# SmartThermo2_1.net
KiCad netlist of a schematic drawn in EAGLE
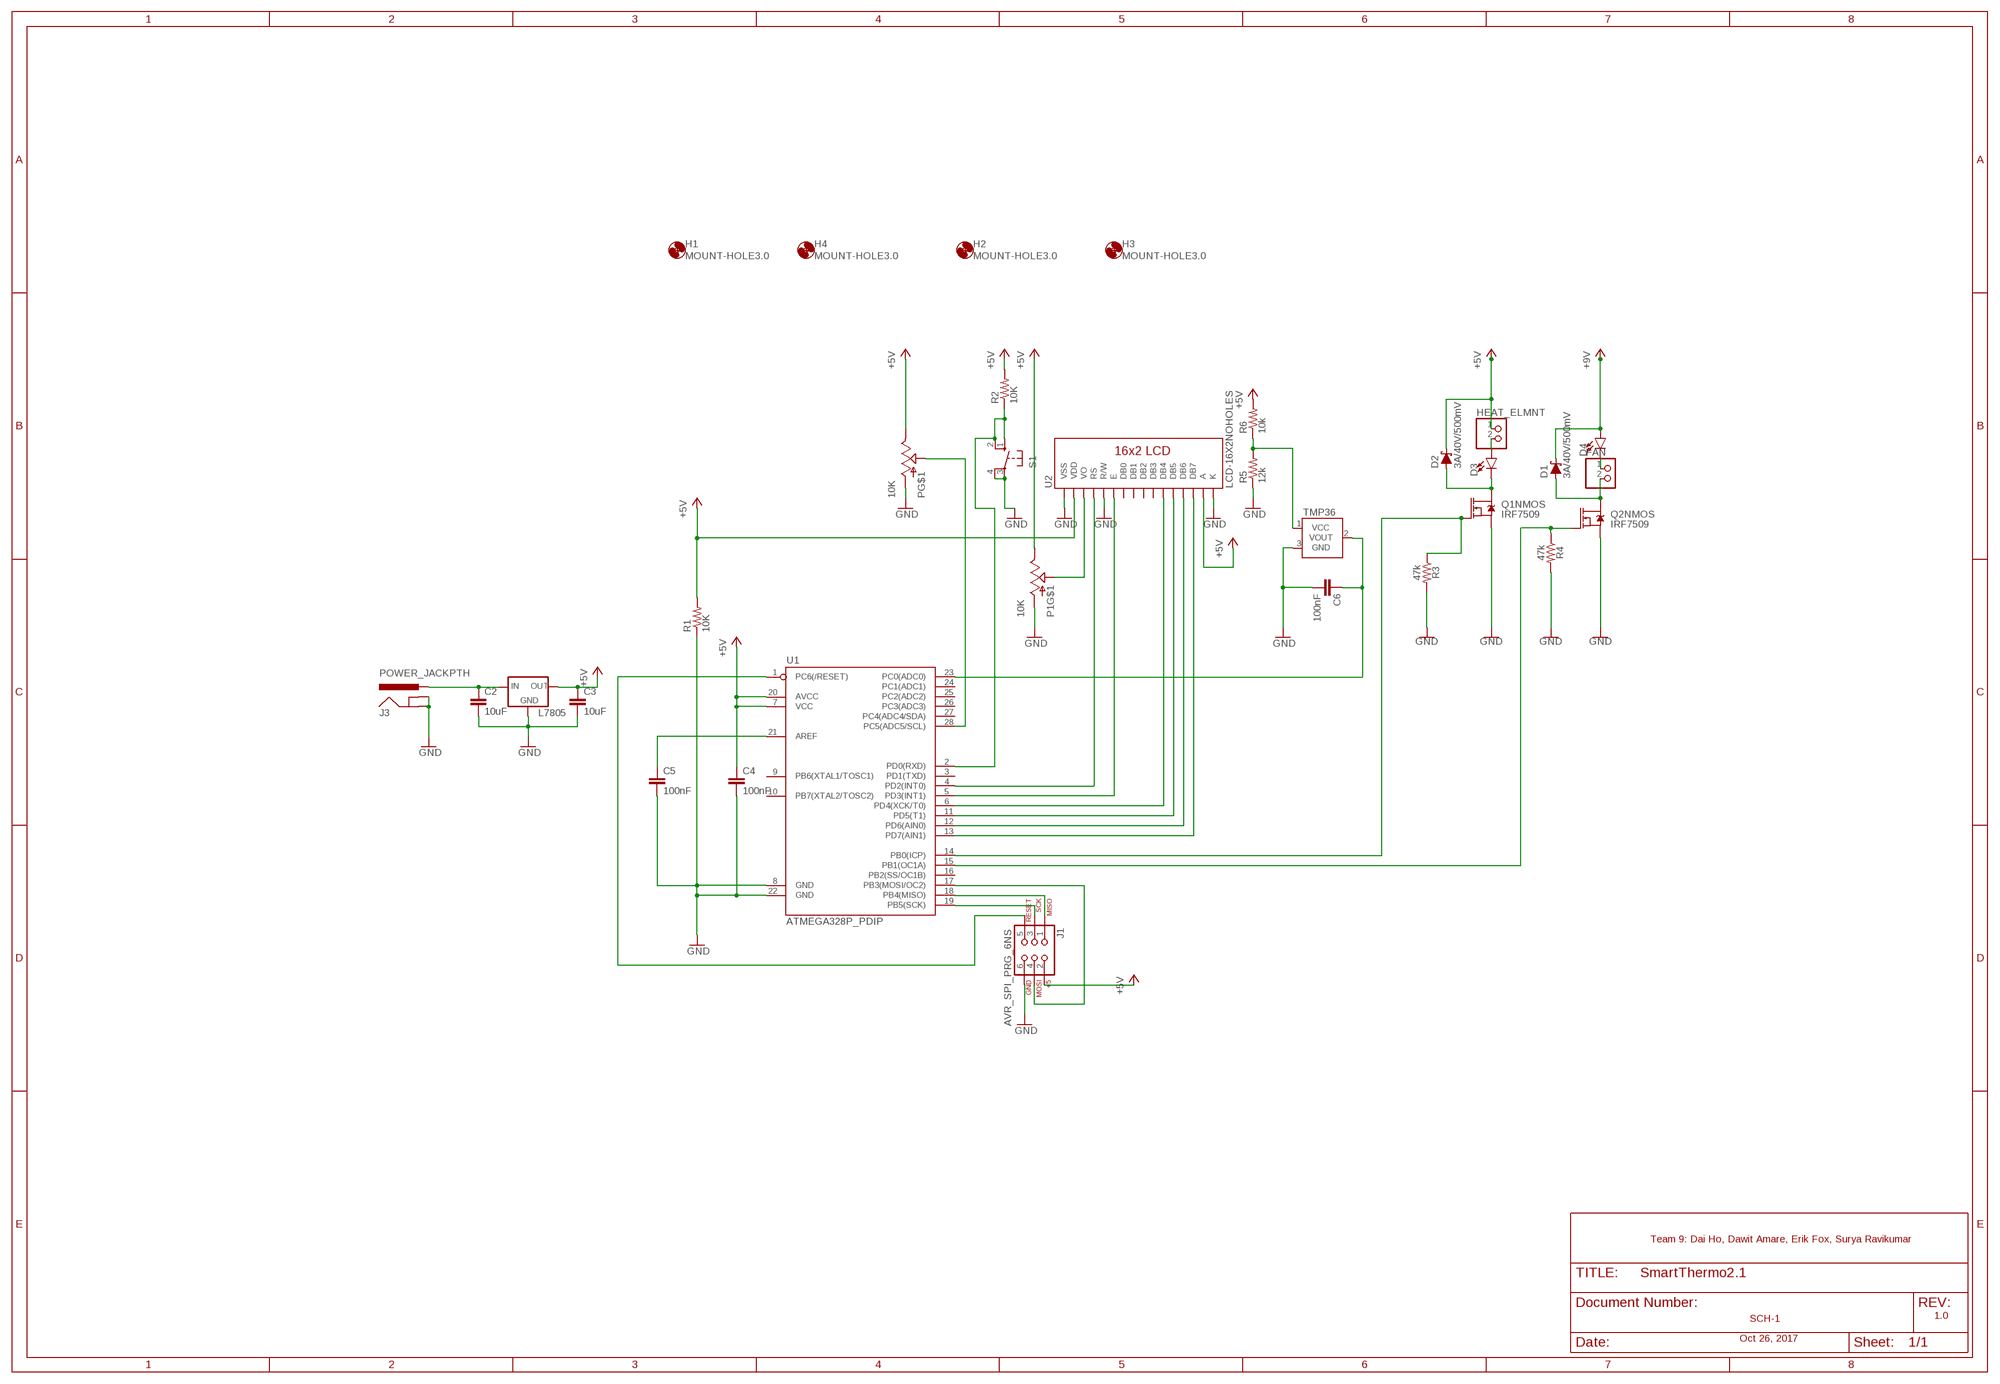
[diagram p0: schematic, sheet 1]

(export (version "E")
  (design (tool "Eeschema 10.0.6"))
  (components
    (comp (ref "C2")
      (value "10uF")
      (footprint "eagle-import:C7.5B3")
      (libsource (lib "eagle-import") (part "C7.5/3"))
    )
    (comp (ref "C3")
      (value "10uF")
      (footprint "eagle-import:C7.5B3")
      (libsource (lib "eagle-import") (part "C7.5/3"))
    )
    (comp (ref "C4")
      (value "100nF")
      (footprint "eagle-import:C2.5-2")
      (libsource (lib "eagle-import") (part "C2.5/2"))
    )
    (comp (ref "C5")
      (value "100nF")
      (footprint "eagle-import:C2.5-2")
      (libsource (lib "eagle-import") (part "C2.5/2"))
    )
    (comp (ref "C6")
      (value "100nF")
      (footprint "eagle-import:C2.5-2")
      (libsource (lib "eagle-import") (part "C2.5/2"))
    )
    (comp (ref "D1")
      (value "3A/40V/500mV")
      (footprint "eagle-import:SMA-DIODE")
      (libsource (lib "eagle-import") (part "DIODE-SCHOTTKY-B340A"))
    )
    (comp (ref "D2")
      (value "3A/40V/500mV")
      (footprint "eagle-import:SMA-DIODE")
      (libsource (lib "eagle-import") (part "DIODE-SCHOTTKY-B340A"))
    )
    (comp (ref "D3")
      (value "LED3MM")
      (footprint "eagle-import:LED_3MM")
      (libsource (lib "eagle-import") (part "LED3MM"))
    )
    (comp (ref "D4")
      (value "LED3MM")
      (footprint "eagle-import:LED_3MM")
      (libsource (lib "eagle-import") (part "LED3MM"))
    )
    (comp (ref "FAN")
      (value "PINHD-1X2/90")
      (footprint "eagle-import:1X02_90")
      (libsource (lib "eagle-import") (part "PINHD-1X2/90"))
    )
    (comp (ref "H1")
      (value "MOUNT-HOLE3.0")
      (footprint "eagle-import:3,0")
      (libsource (lib "eagle-import") (part "MOUNT-HOLE3.0"))
    )
    (comp (ref "H2")
      (value "MOUNT-HOLE3.0")
      (footprint "eagle-import:3,0")
      (libsource (lib "eagle-import") (part "MOUNT-HOLE3.0"))
    )
    (comp (ref "H3")
      (value "MOUNT-HOLE3.0")
      (footprint "eagle-import:3,0")
      (libsource (lib "eagle-import") (part "MOUNT-HOLE3.0"))
    )
    (comp (ref "H4")
      (value "MOUNT-HOLE3.0")
      (footprint "eagle-import:3,0")
      (libsource (lib "eagle-import") (part "MOUNT-HOLE3.0"))
    )
    (comp (ref "HEAT_ELMNT")
      (value "PINHD-1X2/90")
      (footprint "eagle-import:1X02_90")
      (libsource (lib "eagle-import") (part "PINHD-1X2/90"))
    )
    (comp (ref "J1")
      (value "AVR_SPI_PRG_6NS")
      (footprint "eagle-import:2X3-NS")
      (libsource (lib "eagle-import") (part "AVR_SPI_PRG_6NS"))
    )
    (comp (ref "J3")
      (value "POWER_JACKPTH")
      (footprint "eagle-import:POWER_JACK_PTH")
      (libsource (lib "eagle-import") (part "POWER_JACKPTH"))
    )
    (comp (ref "L7805")
      (value "78XXL")
      (footprint "eagle-import:78XXL")
      (libsource (lib "eagle-import") (part "78XXL"))
    )
    (comp (ref "P")
      (value "10K")
      (footprint "eagle-import:POT_PTH")
      (libsource (lib "eagle-import") (part "POT_SWITCHPOT_PTH"))
    )
    (comp (ref "P1")
      (value "10K")
      (footprint "eagle-import:POT_PTH")
      (libsource (lib "eagle-import") (part "POT_SWITCHPOT_PTH"))
    )
    (comp (ref "Q1")
      (value "IRF7509")
      (footprint "eagle-import:MSOP8")
      (libsource (lib "eagle-import") (part "IRF7509"))
    )
    (comp (ref "Q2")
      (value "IRF7509")
      (footprint "eagle-import:MSOP8")
      (libsource (lib "eagle-import") (part "IRF7509"))
    )
    (comp (ref "R1")
      (value "10K")
      (footprint "eagle-import:1206")
      (libsource (lib "eagle-import") (part "RESISTOR1206"))
    )
    (comp (ref "R2")
      (value "10K")
      (footprint "eagle-import:1206")
      (libsource (lib "eagle-import") (part "RESISTOR1206"))
    )
    (comp (ref "R3")
      (value "47k")
      (footprint "eagle-import:0603")
      (libsource (lib "eagle-import") (part "47KOHM-0603-1/10W-1%"))
    )
    (comp (ref "R4")
      (value "47k")
      (footprint "eagle-import:0603")
      (libsource (lib "eagle-import") (part "47KOHM-0603-1/10W-1%"))
    )
    (comp (ref "R5")
      (value "12k")
      (footprint "eagle-import:0204_5")
      (libsource (lib "eagle-import") (part "R-US_0204/5"))
    )
    (comp (ref "R6")
      (value "10k")
      (footprint "eagle-import:0204_5")
      (libsource (lib "eagle-import") (part "R-US_0204/5"))
    )
    (comp (ref "S1")
      (value "10-XX")
      (footprint "eagle-import:B3F-10XX")
      (fields (field (name "MPN") "B3F-1000"))
      (libsource (lib "eagle-import") (part "10-XX"))
    )
    (comp (ref "TMP36")
      (value "TMP36GT9")
      (footprint "eagle-import:TO-92")
      (libsource (lib "eagle-import") (part "TMP36GT9"))
    )
    (comp (ref "U1")
      (value "ATMEGA328P_PDIP")
      (footprint "eagle-import:DIL28-3")
      (libsource (lib "eagle-import") (part "ATMEGA328P_PDIP"))
    )
    (comp (ref "U2")
      (value "LCD-16X2NOHOLES")
      (footprint "eagle-import:LCD-16X2_NOHOLES")
      (libsource (lib "eagle-import") (part "LCD-16X2NOHOLES"))
    )
  )
  (nets
    (net (code "1") (name "+5V") (class "Default")
      (node (ref "C3") (pin "1") (pinfunction "1_1") (pintype "passive"))
      (node (ref "C4") (pin "1") (pinfunction "1_1") (pintype "passive"))
      (node (ref "D1") (pin "C") (pinfunction "C_C") (pintype "passive"))
      (node (ref "D2") (pin "C") (pinfunction "C_C") (pintype "passive"))
      (node (ref "D4") (pin "A") (pinfunction "A_A") (pintype "passive"))
      (node (ref "HEAT_ELMNT") (pin "1") (pinfunction "1_1") (pintype "passive"))
      (node (ref "J1") (pin "2") (pinfunction "2_2") (pintype "passive"))
      (node (ref "L7805") (pin "OUT") (pinfunction "OUT_OUT") (pintype "passive"))
      (node (ref "P") (pin "E@2") (pinfunction "E_E@2") (pintype "passive"))
      (node (ref "P1") (pin "E@2") (pinfunction "E_E@2") (pintype "passive"))
      (node (ref "R1") (pin "2") (pinfunction "2_2") (pintype "passive"))
      (node (ref "R2") (pin "2") (pinfunction "2_2") (pintype "passive"))
      (node (ref "R6") (pin "2") (pinfunction "2_2") (pintype "passive"))
      (node (ref "U1") (pin "20") (pinfunction "AVCC_20") (pintype "bidirectional"))
      (node (ref "U1") (pin "7") (pinfunction "VCC_7") (pintype "bidirectional"))
      (node (ref "U2") (pin "15") (pinfunction "A_15") (pintype "power_in"))
      (node (ref "U2") (pin "2") (pinfunction "VDD_2") (pintype "power_in"))
    )
    (net (code "2") (name "GND") (class "Default")
      (node (ref "C2") (pin "2") (pinfunction "2_2") (pintype "passive"))
      (node (ref "C3") (pin "2") (pinfunction "2_2") (pintype "passive"))
      (node (ref "C4") (pin "2") (pinfunction "2_2") (pintype "passive"))
      (node (ref "C5") (pin "2") (pinfunction "2_2") (pintype "passive"))
      (node (ref "C6") (pin "2") (pinfunction "2_2") (pintype "passive"))
      (node (ref "J1") (pin "6") (pinfunction "6_6") (pintype "passive"))
      (node (ref "J3") (pin "GND") (pinfunction "GND_GND") (pintype "bidirectional"))
      (node (ref "J3") (pin "GNDBREAK") (pinfunction "GNDBREAK_GNDBREAK") (pintype "bidirectional"))
      (node (ref "L7805") (pin "GND") (pinfunction "GND_GND") (pintype "input"))
      (node (ref "P") (pin "E@1") (pinfunction "A_E@1") (pintype "passive"))
      (node (ref "P1") (pin "E@1") (pinfunction "A_E@1") (pintype "passive"))
      (node (ref "Q1") (pin "1") (pinfunction "S_1") (pintype "bidirectional"))
      (node (ref "Q2") (pin "1") (pinfunction "S_1") (pintype "bidirectional"))
      (node (ref "R1") (pin "1") (pinfunction "1_1") (pintype "passive"))
      (node (ref "R3") (pin "2") (pinfunction "2_2") (pintype "passive"))
      (node (ref "R4") (pin "2") (pinfunction "2_2") (pintype "passive"))
      (node (ref "R5") (pin "1") (pinfunction "1_1") (pintype "passive"))
      (node (ref "S1") (pin "3") (pinfunction "P_3") (pintype "passive"))
      (node (ref "S1") (pin "4") (pinfunction "P1_4") (pintype "passive"))
      (node (ref "TMP36") (pin "3") (pinfunction "GND_3") (pintype "bidirectional"))
      (node (ref "U1") (pin "22") (pinfunction "GND_22") (pintype "bidirectional"))
      (node (ref "U1") (pin "8") (pinfunction "GND_8") (pintype "bidirectional"))
      (node (ref "U2") (pin "1") (pinfunction "VSS_1") (pintype "power_in"))
      (node (ref "U2") (pin "16") (pinfunction "K_16") (pintype "power_in"))
      (node (ref "U2") (pin "5") (pinfunction "R/W_5") (pintype "input"))
    )
    (net (code "3") (name "Net-(C2-Pad1)") (class "Default")
      (node (ref "C2") (pin "1") (pinfunction "1_1") (pintype "passive"))
      (node (ref "J3") (pin "PWR") (pinfunction "PWR_PWR") (pintype "bidirectional"))
      (node (ref "L7805") (pin "IN") (pinfunction "IN_IN") (pintype "input"))
    )
    (net (code "4") (name "Net-(D1-PadA)") (class "Default")
      (node (ref "D1") (pin "A") (pinfunction "A_A") (pintype "passive"))
      (node (ref "FAN") (pin "2") (pinfunction "2_2") (pintype "passive"))
      (node (ref "Q2") (pin "7") (pinfunction "D_7") (pintype "bidirectional"))
      (node (ref "Q2") (pin "8") (pinfunction "D_8") (pintype "bidirectional"))
    )
    (net (code "5") (name "Net-(D3-C)") (class "Default")
      (node (ref "D2") (pin "A") (pinfunction "A_A") (pintype "passive"))
      (node (ref "D3") (pin "K") (pinfunction "C_K") (pintype "passive"))
      (node (ref "Q1") (pin "7") (pinfunction "D_7") (pintype "bidirectional"))
      (node (ref "Q1") (pin "8") (pinfunction "D_8") (pintype "bidirectional"))
    )
    (net (code "6") (name "Net-(D3-PadA)") (class "Default")
      (node (ref "D3") (pin "A") (pinfunction "A_A") (pintype "passive"))
      (node (ref "HEAT_ELMNT") (pin "2") (pinfunction "2_2") (pintype "passive"))
    )
    (net (code "7") (name "Net-(D4-C)") (class "Default")
      (node (ref "D4") (pin "K") (pinfunction "C_K") (pintype "passive"))
      (node (ref "FAN") (pin "1") (pinfunction "1_1") (pintype "passive"))
    )
    (net (code "8") (name "Net-(P1A-S)") (class "Default")
      (node (ref "P1") (pin "WAND") (pinfunction "S_WAND") (pintype "passive"))
      (node (ref "U2") (pin "3") (pinfunction "VO_3") (pintype "bidirectional"))
    )
    (net (code "9") (name "Net-(PA-S)") (class "Default")
      (node (ref "P") (pin "WAND") (pinfunction "S_WAND") (pintype "passive"))
      (node (ref "U1") (pin "28") (pinfunction "PC5(ADC5/SCL)_28") (pintype "bidirectional"))
    )
    (net (code "10") (name "Net-(Q1A-G)") (class "Default")
      (node (ref "Q1") (pin "2") (pinfunction "G_2") (pintype "bidirectional"))
      (node (ref "R3") (pin "1") (pinfunction "1_1") (pintype "passive"))
      (node (ref "U1") (pin "14") (pinfunction "PB0(ICP)_14") (pintype "bidirectional"))
    )
    (net (code "11") (name "Net-(Q2A-G)") (class "Default")
      (node (ref "Q2") (pin "2") (pinfunction "G_2") (pintype "bidirectional"))
      (node (ref "R4") (pin "1") (pinfunction "1_1") (pintype "passive"))
      (node (ref "U1") (pin "15") (pinfunction "PB1(OC1A)_15") (pintype "bidirectional"))
    )
    (net (code "12") (name "Net-(S1-S)") (class "Default")
      (node (ref "R2") (pin "1") (pinfunction "1_1") (pintype "passive"))
      (node (ref "S1") (pin "1") (pinfunction "S_1") (pintype "passive"))
      (node (ref "S1") (pin "2") (pinfunction "S1_2") (pintype "passive"))
      (node (ref "U1") (pin "2") (pinfunction "PD0(RXD)_2") (pintype "bidirectional"))
    )
    (net (code "13") (name "Net-(TMP36-VCC)") (class "Default")
      (node (ref "R5") (pin "2") (pinfunction "2_2") (pintype "passive"))
      (node (ref "R6") (pin "1") (pinfunction "1_1") (pintype "passive"))
      (node (ref "TMP36") (pin "1") (pinfunction "VCC_1") (pintype "bidirectional"))
    )
    (net (code "14") (name "Net-(TMP36-VOUT)") (class "Default")
      (node (ref "C6") (pin "1") (pinfunction "1_1") (pintype "passive"))
      (node (ref "TMP36") (pin "2") (pinfunction "VOUT_2") (pintype "bidirectional"))
      (node (ref "U1") (pin "23") (pinfunction "PC0(ADC0)_23") (pintype "bidirectional"))
    )
    (net (code "15") (name "Net-(U1-AREF)") (class "Default")
      (node (ref "C5") (pin "1") (pinfunction "1_1") (pintype "passive"))
      (node (ref "U1") (pin "21") (pinfunction "AREF_21") (pintype "bidirectional"))
    )
    (net (code "16") (name "Net-(U1-PB3(MOSI{slash}OC2))") (class "Default")
      (node (ref "J1") (pin "4") (pinfunction "4_4") (pintype "passive"))
      (node (ref "U1") (pin "17") (pinfunction "PB3(MOSI/OC2)_17") (pintype "bidirectional"))
    )
    (net (code "17") (name "Net-(U1-PB4(MISO))") (class "Default")
      (node (ref "J1") (pin "1") (pinfunction "1_1") (pintype "passive"))
      (node (ref "U1") (pin "18") (pinfunction "PB4(MISO)_18") (pintype "bidirectional"))
    )
    (net (code "18") (name "Net-(U1-PB5(SCK))") (class "Default")
      (node (ref "J1") (pin "3") (pinfunction "3_3") (pintype "passive"))
      (node (ref "U1") (pin "19") (pinfunction "PB5(SCK)_19") (pintype "bidirectional"))
    )
    (net (code "19") (name "Net-(U1-PC6({slash}RESET))") (class "Default")
      (node (ref "J1") (pin "5") (pinfunction "5_5") (pintype "passive"))
      (node (ref "U1") (pin "1") (pinfunction "PC6(/RESET)_1") (pintype "bidirectional"))
    )
    (net (code "20") (name "Net-(U1-PD2(INT0))") (class "Default")
      (node (ref "U1") (pin "4") (pinfunction "PD2(INT0)_4") (pintype "bidirectional"))
      (node (ref "U2") (pin "4") (pinfunction "RS_4") (pintype "input"))
    )
    (net (code "21") (name "Net-(U1-PD3(INT1))") (class "Default")
      (node (ref "U1") (pin "5") (pinfunction "PD3(INT1)_5") (pintype "bidirectional"))
      (node (ref "U2") (pin "6") (pinfunction "E_6") (pintype "input"))
    )
    (net (code "22") (name "Net-(U1-PD4(XCK{slash}T0))") (class "Default")
      (node (ref "U1") (pin "6") (pinfunction "PD4(XCK/T0)_6") (pintype "bidirectional"))
      (node (ref "U2") (pin "11") (pinfunction "DB4_11") (pintype "bidirectional"))
    )
    (net (code "23") (name "Net-(U1-PD5(T1))") (class "Default")
      (node (ref "U1") (pin "11") (pinfunction "PD5(T1)_11") (pintype "bidirectional"))
      (node (ref "U2") (pin "12") (pinfunction "DB5_12") (pintype "bidirectional"))
    )
    (net (code "24") (name "Net-(U1-PD6(AIN0))") (class "Default")
      (node (ref "U1") (pin "12") (pinfunction "PD6(AIN0)_12") (pintype "bidirectional"))
      (node (ref "U2") (pin "13") (pinfunction "DB6_13") (pintype "bidirectional"))
    )
    (net (code "25") (name "Net-(U1-PD7(AIN1))") (class "Default")
      (node (ref "U1") (pin "13") (pinfunction "PD7(AIN1)_13") (pintype "bidirectional"))
      (node (ref "U2") (pin "14") (pinfunction "DB7_14") (pintype "bidirectional"))
    )
    (net (code "26") (name "unconnected-(U1-PB2(SS{slash}OC1B)-Pad16)") (class "Default")
      (node (ref "U1") (pin "16") (pinfunction "PB2(SS/OC1B)_16") (pintype "bidirectional"))
    )
    (net (code "27") (name "unconnected-(U1-PB6(XTAL1{slash}TOSC1)-Pad9)") (class "Default")
      (node (ref "U1") (pin "9") (pinfunction "PB6(XTAL1/TOSC1)_9") (pintype "bidirectional"))
    )
    (net (code "28") (name "unconnected-(U1-PB7(XTAL2{slash}TOSC2)-Pad10)") (class "Default")
      (node (ref "U1") (pin "10") (pinfunction "PB7(XTAL2/TOSC2)_10") (pintype "bidirectional"))
    )
    (net (code "29") (name "unconnected-(U1-PC1(ADC1)-Pad24)") (class "Default")
      (node (ref "U1") (pin "24") (pinfunction "PC1(ADC1)_24") (pintype "bidirectional"))
    )
    (net (code "30") (name "unconnected-(U1-PC2(ADC2)-Pad25)") (class "Default")
      (node (ref "U1") (pin "25") (pinfunction "PC2(ADC2)_25") (pintype "bidirectional"))
    )
    (net (code "31") (name "unconnected-(U1-PC3(ADC3)-Pad26)") (class "Default")
      (node (ref "U1") (pin "26") (pinfunction "PC3(ADC3)_26") (pintype "bidirectional"))
    )
    (net (code "32") (name "unconnected-(U1-PC4(ADC4{slash}SDA)-Pad27)") (class "Default")
      (node (ref "U1") (pin "27") (pinfunction "PC4(ADC4/SDA)_27") (pintype "bidirectional"))
    )
    (net (code "33") (name "unconnected-(U1-PD1(TXD)-Pad3)") (class "Default")
      (node (ref "U1") (pin "3") (pinfunction "PD1(TXD)_3") (pintype "bidirectional"))
    )
    (net (code "34") (name "unconnected-(U2-DB0-Pad7)") (class "Default")
      (node (ref "U2") (pin "7") (pinfunction "DB0_7") (pintype "bidirectional"))
    )
    (net (code "35") (name "unconnected-(U2-DB1-Pad8)") (class "Default")
      (node (ref "U2") (pin "8") (pinfunction "DB1_8") (pintype "bidirectional"))
    )
    (net (code "36") (name "unconnected-(U2-DB2-Pad9)") (class "Default")
      (node (ref "U2") (pin "9") (pinfunction "DB2_9") (pintype "bidirectional"))
    )
    (net (code "37") (name "unconnected-(U2-DB3-Pad10)") (class "Default")
      (node (ref "U2") (pin "10") (pinfunction "DB3_10") (pintype "bidirectional"))
    )
  )
)
